# partes_proyecto.net
KiCad netlist of a schematic drawn in Altium Designer
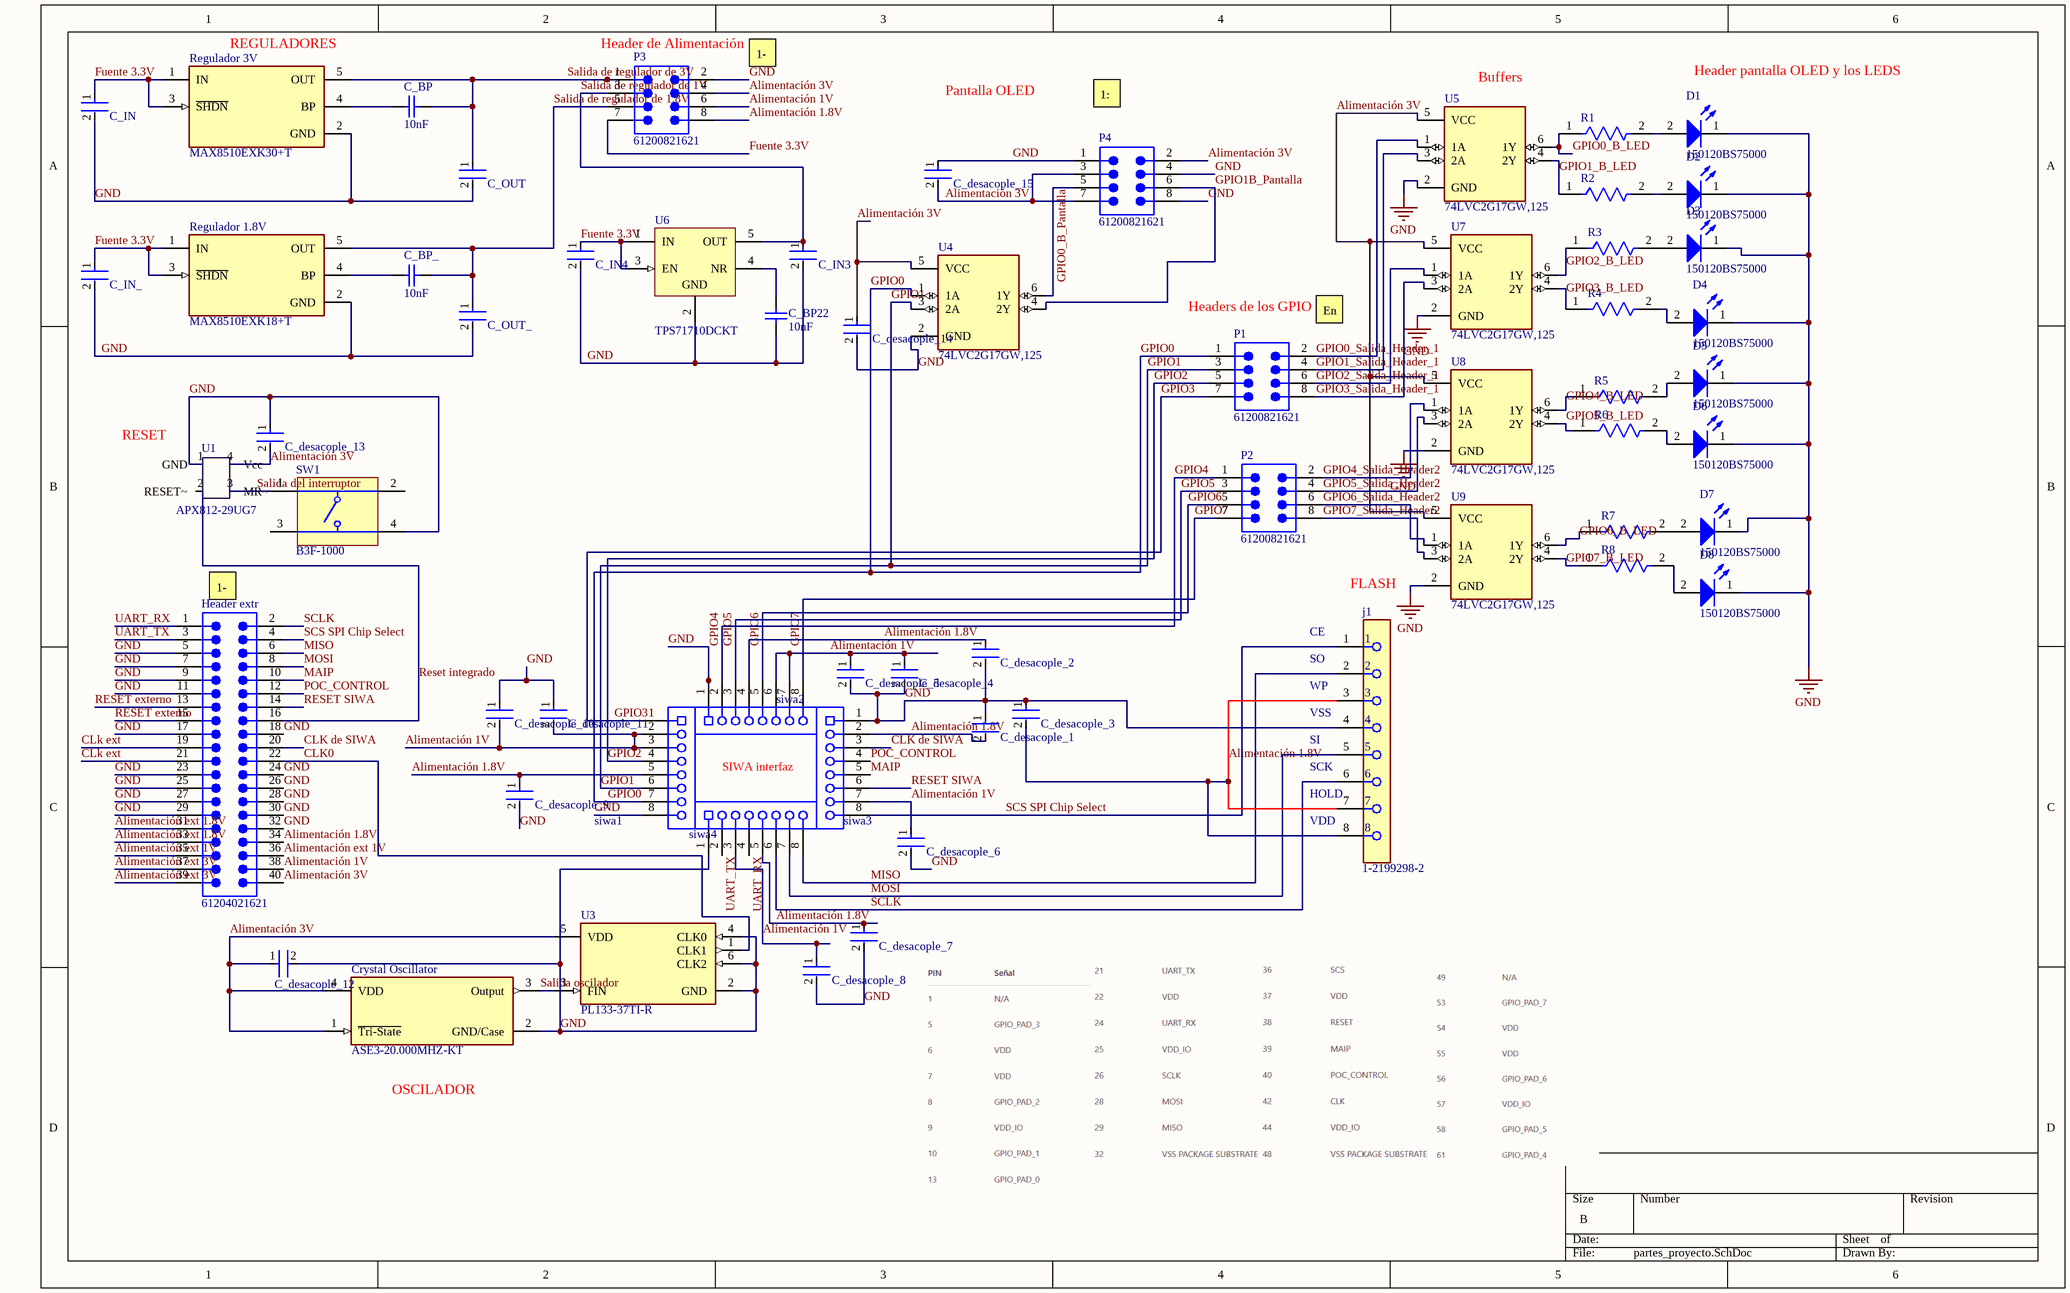
[diagram p0: partes_proyecto.SchDoc]

(export (version "E")
  (design (tool "Eeschema 10.0.6"))
  (components
    (comp (ref "Crystal Oscillator")
      (value "ASE3-20.000MHZ-KT")
      (footprint "FP-ASE3-MFG")
      (description "XTAL OSC XO 20.0000MHZ CMOS SMD")
      (libsource (lib "Altium Content Vault") (part "37c4c26fe5ae6223af2046a137c0b30"))
    )
    (comp (ref "C_BP")
      (value "10nF")
      (footprint "CAPC2013X100X50NL20T25")
      (fields (field (name "PART NUMBER") "C0805F103K5RACTU") (field (name "MANUFACTURER") "Kemet"))
      (libsource (lib "Altium Content Vault") (part "CAP"))
    )
    (comp (ref "C_BP22")
      (value "10nF")
      (footprint "CAPC2013X100X50NL20T25")
      (fields (field (name "PART NUMBER") "C0805F103K5RACTU") (field (name "MANUFACTURER") "Kemet"))
      (libsource (lib "Altium Content Vault") (part "CAP"))
    )
    (comp (ref "C_BP_")
      (value "10nF")
      (footprint "CAPC2013X100X50NL20T25")
      (fields (field (name "PART NUMBER") "C0805F103K5RACTU") (field (name "MANUFACTURER") "Kemet"))
      (libsource (lib "Altium Content Vault") (part "CAP"))
    )
    (comp (ref "C_desacople_1")
      (value "CC0603KRX7R7BB104")
      (footprint "FP-CC0603-DA-MFG")
      (description "CAP CER 0.1UF 16V X7R 0603")
      (fields
        (field (name "OCTOPART") "https://octopart.com/cc0603krx7r7bb104-yageo-192941")
        (field (name "TOLERANCE") "0.1")
      )
      (libsource (lib "Altium Content Vault") (part "11868f565c42a9108669ba33697ecf6"))
    )
    (comp (ref "C_desacople_2")
      (value "CC0603KRX7R7BB104")
      (footprint "FP-CC0603-DA-MFG")
      (description "CAP CER 0.1UF 16V X7R 0603")
      (fields
        (field (name "OCTOPART") "https://octopart.com/cc0603krx7r7bb104-yageo-192941")
        (field (name "TOLERANCE") "0.1")
      )
      (libsource (lib "Altium Content Vault") (part "11868f565c42a9108669ba33697ecf6"))
    )
    (comp (ref "C_desacople_3")
      (value "CC0603KRX7R7BB104")
      (footprint "FP-CC0603-DA-MFG")
      (description "CAP CER 0.1UF 16V X7R 0603")
      (fields
        (field (name "OCTOPART") "https://octopart.com/cc0603krx7r7bb104-yageo-192941")
        (field (name "TOLERANCE") "0.1")
      )
      (libsource (lib "Altium Content Vault") (part "11868f565c42a9108669ba33697ecf6"))
    )
    (comp (ref "C_desacople_4")
      (value "CC0603KRX7R7BB104")
      (footprint "FP-CC0603-DA-MFG")
      (description "CAP CER 0.1UF 16V X7R 0603")
      (fields
        (field (name "OCTOPART") "https://octopart.com/cc0603krx7r7bb104-yageo-192941")
        (field (name "TOLERANCE") "0.1")
      )
      (libsource (lib "Altium Content Vault") (part "11868f565c42a9108669ba33697ecf6"))
    )
    (comp (ref "C_desacople_5")
      (value "CC0603KRX7R7BB104")
      (footprint "FP-CC0603-DA-MFG")
      (description "CAP CER 0.1UF 16V X7R 0603")
      (fields
        (field (name "OCTOPART") "https://octopart.com/cc0603krx7r7bb104-yageo-192941")
        (field (name "TOLERANCE") "0.1")
      )
      (libsource (lib "Altium Content Vault") (part "11868f565c42a9108669ba33697ecf6"))
    )
    (comp (ref "C_desacople_6")
      (value "CC0603KRX7R7BB104")
      (footprint "FP-CC0603-DA-MFG")
      (description "CAP CER 0.1UF 16V X7R 0603")
      (fields
        (field (name "OCTOPART") "https://octopart.com/cc0603krx7r7bb104-yageo-192941")
        (field (name "TOLERANCE") "0.1")
      )
      (libsource (lib "Altium Content Vault") (part "11868f565c42a9108669ba33697ecf6"))
    )
    (comp (ref "C_desacople_7")
      (value "CC0603KRX7R7BB104")
      (footprint "FP-CC0603-DA-MFG")
      (description "CAP CER 0.1UF 16V X7R 0603")
      (fields
        (field (name "OCTOPART") "https://octopart.com/cc0603krx7r7bb104-yageo-192941")
        (field (name "TOLERANCE") "0.1")
      )
      (libsource (lib "Altium Content Vault") (part "11868f565c42a9108669ba33697ecf6"))
    )
    (comp (ref "C_desacople_8")
      (value "CC0603KRX7R7BB104")
      (footprint "FP-CC0603-DA-MFG")
      (description "CAP CER 0.1UF 16V X7R 0603")
      (fields
        (field (name "OCTOPART") "https://octopart.com/cc0603krx7r7bb104-yageo-192941")
        (field (name "TOLERANCE") "0.1")
      )
      (libsource (lib "Altium Content Vault") (part "11868f565c42a9108669ba33697ecf6"))
    )
    (comp (ref "C_desacople_9")
      (value "CC0603KRX7R7BB104")
      (footprint "FP-CC0603-DA-MFG")
      (description "CAP CER 0.1UF 16V X7R 0603")
      (fields
        (field (name "OCTOPART") "https://octopart.com/cc0603krx7r7bb104-yageo-192941")
        (field (name "TOLERANCE") "0.1")
      )
      (libsource (lib "Altium Content Vault") (part "11868f565c42a9108669ba33697ecf6"))
    )
    (comp (ref "C_desacople_10")
      (value "CC0603KRX7R7BB104")
      (footprint "FP-CC0603-DA-MFG")
      (description "CAP CER 0.1UF 16V X7R 0603")
      (fields
        (field (name "OCTOPART") "https://octopart.com/cc0603krx7r7bb104-yageo-192941")
        (field (name "TOLERANCE") "0.1")
      )
      (libsource (lib "Altium Content Vault") (part "11868f565c42a9108669ba33697ecf6"))
    )
    (comp (ref "C_desacople_11")
      (value "CC0603KRX7R7BB104")
      (footprint "FP-CC0603-DA-MFG")
      (description "CAP CER 0.1UF 16V X7R 0603")
      (fields
        (field (name "OCTOPART") "https://octopart.com/cc0603krx7r7bb104-yageo-192941")
        (field (name "TOLERANCE") "0.1")
      )
      (libsource (lib "Altium Content Vault") (part "11868f565c42a9108669ba33697ecf6"))
    )
    (comp (ref "C_desacople_12")
      (value "CC0603KRX7R7BB104")
      (footprint "FP-CC0603-DA-MFG")
      (description "CAP CER 0.1UF 16V X7R 0603")
      (fields
        (field (name "OCTOPART") "https://octopart.com/cc0603krx7r7bb104-yageo-192941")
        (field (name "TOLERANCE") "0.1")
      )
      (libsource (lib "Altium Content Vault") (part "11868f565c42a9108669ba33697ecf6"))
    )
    (comp (ref "C_desacople_13")
      (value "CC0603KRX7R7BB104")
      (footprint "FP-CC0603-DA-MFG")
      (description "CAP CER 0.1UF 16V X7R 0603")
      (fields
        (field (name "OCTOPART") "https://octopart.com/cc0603krx7r7bb104-yageo-192941")
        (field (name "TOLERANCE") "0.1")
      )
      (libsource (lib "Altium Content Vault") (part "11868f565c42a9108669ba33697ecf6"))
    )
    (comp (ref "C_desacople_14")
      (value "CC0603KRX7R7BB104")
      (footprint "FP-CC0603-DA-MFG")
      (description "CAP CER 0.1UF 16V X7R 0603")
      (fields
        (field (name "OCTOPART") "https://octopart.com/cc0603krx7r7bb104-yageo-192941")
        (field (name "TOLERANCE") "0.1")
      )
      (libsource (lib "Altium Content Vault") (part "11868f565c42a9108669ba33697ecf6"))
    )
    (comp (ref "C_desacople_15")
      (value "CC0603KRX7R7BB104")
      (footprint "FP-CC0603-DA-MFG")
      (description "CAP CER 0.1UF 16V X7R 0603")
      (fields
        (field (name "OCTOPART") "https://octopart.com/cc0603krx7r7bb104-yageo-192941")
        (field (name "TOLERANCE") "0.1")
      )
      (libsource (lib "Altium Content Vault") (part "11868f565c42a9108669ba33697ecf6"))
    )
    (comp (ref "C_IN")
      (value "CC0603KRX7R7BB104")
      (footprint "FP-CC0603-DA-MFG")
      (description "CAP CER 0.1UF 16V X7R 0603")
      (fields
        (field (name "OCTOPART") "https://octopart.com/cc0603krx7r7bb104-yageo-192941")
        (field (name "TOLERANCE") "0.1")
      )
      (libsource (lib "Altium Content Vault") (part "11868f565c42a9108669ba33697ecf6"))
    )
    (comp (ref "C_IN3")
      (value "CC0603KRX7R7BB104")
      (footprint "FP-CC0603-DA-MFG")
      (description "CAP CER 0.1UF 16V X7R 0603")
      (fields
        (field (name "OCTOPART") "https://octopart.com/cc0603krx7r7bb104-yageo-192941")
        (field (name "TOLERANCE") "0.1")
      )
      (libsource (lib "Altium Content Vault") (part "11868f565c42a9108669ba33697ecf6"))
    )
    (comp (ref "C_IN4")
      (value "CC0603KRX7R7BB104")
      (footprint "FP-CC0603-DA-MFG")
      (description "CAP CER 0.1UF 16V X7R 0603")
      (fields
        (field (name "OCTOPART") "https://octopart.com/cc0603krx7r7bb104-yageo-192941")
        (field (name "TOLERANCE") "0.1")
      )
      (libsource (lib "Altium Content Vault") (part "11868f565c42a9108669ba33697ecf6"))
    )
    (comp (ref "C_IN_")
      (value "CC0603KRX7R7BB104")
      (footprint "FP-CC0603-DA-MFG")
      (description "CAP CER 0.1UF 16V X7R 0603")
      (fields
        (field (name "OCTOPART") "https://octopart.com/cc0603krx7r7bb104-yageo-192941")
        (field (name "TOLERANCE") "0.1")
      )
      (libsource (lib "Altium Content Vault") (part "11868f565c42a9108669ba33697ecf6"))
    )
    (comp (ref "C_OUT")
      (value "CC0603KRX7R7BB104")
      (footprint "FP-CC0603-DA-MFG")
      (description "CAP CER 0.1UF 16V X7R 0603")
      (fields
        (field (name "OCTOPART") "https://octopart.com/cc0603krx7r7bb104-yageo-192941")
        (field (name "TOLERANCE") "0.1")
      )
      (libsource (lib "Altium Content Vault") (part "11868f565c42a9108669ba33697ecf6"))
    )
    (comp (ref "C_OUT_")
      (value "CC0603KRX7R7BB104")
      (footprint "FP-CC0603-DA-MFG")
      (description "CAP CER 0.1UF 16V X7R 0603")
      (fields
        (field (name "OCTOPART") "https://octopart.com/cc0603krx7r7bb104-yageo-192941")
        (field (name "TOLERANCE") "0.1")
      )
      (libsource (lib "Altium Content Vault") (part "11868f565c42a9108669ba33697ecf6"))
    )
    (comp (ref "D1")
      (value "150120BS75000")
      (footprint "WL-SMCW_1206_150120xx75000")
      (description "WL-SMCW SMT Mono-Color Chip LED Waterclear")
      (libsource (lib "Altium Content Vault") (part "LED_Blue_2A-1K"))
    )
    (comp (ref "D2")
      (value "150120BS75000")
      (footprint "WL-SMCW_1206_150120xx75000")
      (description "WL-SMCW SMT Mono-Color Chip LED Waterclear")
      (libsource (lib "Altium Content Vault") (part "LED_Blue_2A-1K"))
    )
    (comp (ref "D3")
      (value "150120BS75000")
      (footprint "WL-SMCW_1206_150120xx75000")
      (description "WL-SMCW SMT Mono-Color Chip LED Waterclear")
      (libsource (lib "Altium Content Vault") (part "LED_Blue_2A-1K"))
    )
    (comp (ref "D4")
      (value "150120BS75000")
      (footprint "WL-SMCW_1206_150120xx75000")
      (description "WL-SMCW SMT Mono-Color Chip LED Waterclear")
      (libsource (lib "Altium Content Vault") (part "LED_Blue_2A-1K"))
    )
    (comp (ref "D5")
      (value "150120BS75000")
      (footprint "WL-SMCW_1206_150120xx75000")
      (description "WL-SMCW SMT Mono-Color Chip LED Waterclear")
      (libsource (lib "Altium Content Vault") (part "LED_Blue_2A-1K"))
    )
    (comp (ref "D6")
      (value "150120BS75000")
      (footprint "WL-SMCW_1206_150120xx75000")
      (description "WL-SMCW SMT Mono-Color Chip LED Waterclear")
      (libsource (lib "Altium Content Vault") (part "LED_Blue_2A-1K"))
    )
    (comp (ref "D7")
      (value "150120BS75000")
      (footprint "WL-SMCW_1206_150120xx75000")
      (description "WL-SMCW SMT Mono-Color Chip LED Waterclear")
      (libsource (lib "Altium Content Vault") (part "LED_Blue_2A-1K"))
    )
    (comp (ref "D8")
      (value "150120BS75000")
      (footprint "WL-SMCW_1206_150120xx75000")
      (description "WL-SMCW SMT Mono-Color Chip LED Waterclear")
      (libsource (lib "Altium Content Vault") (part "LED_Blue_2A-1K"))
    )
    (comp (ref "Header extr")
      (value "61204021621")
      (footprint "61204021621")
      (libsource (lib "Altium Content Vault") (part "Header_Male_2R_40P"))
    )
    (comp (ref "j1")
      (value "1-2199298-2")
      (footprint "FP-1-2199298-2-MFG")
      (description "CONN IC DIP SOCKET 8POS TIN")
      (libsource (lib "Altium Content Vault") (part "b0a0b555dd3abf3683e7c330df25cc4"))
    )
    (comp (ref "P1")
      (value "61200821621")
      (footprint "61200821621")
      (libsource (lib "Altium Content Vault") (part "Header_Male_2R_08P"))
    )
    (comp (ref "P2")
      (value "61200821621")
      (footprint "61200821621")
      (libsource (lib "Altium Content Vault") (part "Header_Male_2R_08P"))
    )
    (comp (ref "P3")
      (value "61200821621")
      (footprint "61200821621")
      (libsource (lib "Altium Content Vault") (part "Header_Male_2R_08P"))
    )
    (comp (ref "P4")
      (value "61200821621")
      (footprint "61200821621")
      (libsource (lib "Altium Content Vault") (part "Header_Male_2R_08P"))
    )
    (comp (ref "R1")
      (value "10")
      (footprint "FP-MCT0603-IPC_A")
      (description "RES SMD 100 OHM 1% 1/8W 0603")
      (fields (field (name "TOLERANCE") "0.1%"))
      (libsource (lib "Altium Content Vault") (part "1029c3af85768c4190bb7ad29bc67b5"))
    )
    (comp (ref "R2")
      (value "10")
      (footprint "FP-MCT0603-IPC_A")
      (description "RES SMD 100 OHM 1% 1/8W 0603")
      (fields (field (name "TOLERANCE") "0.1%"))
      (libsource (lib "Altium Content Vault") (part "1029c3af85768c4190bb7ad29bc67b5"))
    )
    (comp (ref "R3")
      (value "10")
      (footprint "FP-MCT0603-IPC_A")
      (description "RES SMD 100 OHM 1% 1/8W 0603")
      (fields (field (name "TOLERANCE") "0.1%"))
      (libsource (lib "Altium Content Vault") (part "1029c3af85768c4190bb7ad29bc67b5"))
    )
    (comp (ref "R4")
      (value "10")
      (footprint "FP-MCT0603-IPC_A")
      (description "RES SMD 100 OHM 1% 1/8W 0603")
      (fields (field (name "TOLERANCE") "0.1%"))
      (libsource (lib "Altium Content Vault") (part "1029c3af85768c4190bb7ad29bc67b5"))
    )
    (comp (ref "R5")
      (value "10")
      (footprint "FP-MCT0603-IPC_A")
      (description "RES SMD 100 OHM 1% 1/8W 0603")
      (fields (field (name "TOLERANCE") "0.1%"))
      (libsource (lib "Altium Content Vault") (part "1029c3af85768c4190bb7ad29bc67b5"))
    )
    (comp (ref "R6")
      (value "10")
      (footprint "FP-MCT0603-IPC_A")
      (description "RES SMD 100 OHM 1% 1/8W 0603")
      (fields (field (name "TOLERANCE") "0.1%"))
      (libsource (lib "Altium Content Vault") (part "1029c3af85768c4190bb7ad29bc67b5"))
    )
    (comp (ref "R7")
      (value "10")
      (footprint "FP-MCT0603-IPC_A")
      (description "RES SMD 100 OHM 1% 1/8W 0603")
      (fields (field (name "TOLERANCE") "0.1%"))
      (libsource (lib "Altium Content Vault") (part "1029c3af85768c4190bb7ad29bc67b5"))
    )
    (comp (ref "R8")
      (value "10")
      (footprint "FP-MCT0603-IPC_A")
      (description "RES SMD 100 OHM 1% 1/8W 0603")
      (fields (field (name "TOLERANCE") "0.1%"))
      (libsource (lib "Altium Content Vault") (part "1029c3af85768c4190bb7ad29bc67b5"))
    )
    (comp (ref "Regulador 1.8V")
      (value "MAX8510EXK18+T")
      (footprint "FP-X5-1-MFG")
      (description "IC REG LINEAR 1.8V 120MA SC70-5")
      (libsource (lib "Altium Content Vault") (part "355d6218c957986cfc1b3588039a240"))
    )
    (comp (ref "Regulador 3V")
      (value "MAX8510EXK30+T")
      (footprint "FP-X5-1-MFG")
      (description "IC REG LINEAR 3V 120MA SC70-5")
      (libsource (lib "Altium Content Vault") (part "355d6218c957986cfc1b3588039a240"))
    )
    (comp (ref "siwa1")
      (value "PPPC081LFBN-RC")
      (footprint "SLIN-PPPC081LFBN-RC_V")
      (libsource (lib "") (part "CN-1P-F-R8_2"))
    )
    (comp (ref "siwa2")
      (value "PPPC081LFBN-RC")
      (footprint "SLIN-PPPC081LFBN-RC_V")
      (libsource (lib "") (part "CN-1P-F-R8_1"))
    )
    (comp (ref "siwa3")
      (value "PPPC081LFBN-RC")
      (footprint "SLIN-PPPC081LFBN-RC_V")
      (libsource (lib "") (part "CN-1P-F-R8_3"))
    )
    (comp (ref "siwa4")
      (value "PPPC081LFBN-RC")
      (footprint "SLIN-PPPC081LFBN-RC_V")
      (libsource (lib "Altium Content Vault") (part "CN-1P-F-R8"))
    )
    (comp (ref "SW1")
      (value "B3F-1000")
      (footprint "OMRON-B3F-1000-4_V")
      (description "Tactile Switch, SPST-NO, 0.05 A, 5 to 24 V, -25 to 70 degC, 4-Pin THD, RoHS, Bulk")
      (libsource (lib "Altium Content Vault") (part "SW-SPST-4_A"))
    )
    (comp (ref "U1")
      (value "APX812-29UG7")
      (footprint "APX812-29UG7")
      (description "4-Pin Microprocessor Supervisor With Manual Reset. SOT143.")
      (libsource (lib "Schlib1") (part "APX812-29UG7"))
    )
    (comp (ref "U3")
      (value "PL133-37TI-R")
      (footprint "FP-SOT23-6LD-PL-1-IPC_A")
      (description "IC CLK BUFFER 1:3 150MHZ 6SOT23")
      (libsource (lib "Altium Content Vault") (part "fd8087dcb4da491d5d9bef7da23e705"))
    )
    (comp (ref "U4")
      (value "74LVC2G17GW,125")
      (footprint "SOT363_INFINEON")
      (libsource (lib "Schlib1") (part "74LVC2G17GW,125"))
    )
    (comp (ref "U5")
      (value "74LVC2G17GW,125")
      (footprint "SOT363_INFINEON")
      (libsource (lib "Schlib1") (part "74LVC2G17GW,125"))
    )
    (comp (ref "U6")
      (value "TPS71710DCKT")
      (footprint "DCK0005A_M")
      (fields (field (name "MANUFACTURER") "Texas Instruments"))
      (libsource (lib "Altium Content Vault") (part "TI-TPS79NXX-YYSOT5"))
    )
    (comp (ref "U7")
      (value "74LVC2G17GW,125")
      (footprint "SOT363_INFINEON")
      (libsource (lib "Schlib1") (part "74LVC2G17GW,125"))
    )
    (comp (ref "U8")
      (value "74LVC2G17GW,125")
      (footprint "SOT363_INFINEON")
      (libsource (lib "Schlib1") (part "74LVC2G17GW,125"))
    )
    (comp (ref "U9")
      (value "74LVC2G17GW,125")
      (footprint "SOT363_INFINEON")
      (libsource (lib "Schlib1") (part "74LVC2G17GW,125"))
    )
  )
  (nets
    (net (code "2") (name "/Alimentación 1.8V") (class "Default")
      (node (ref "C_desacople_1") (pin "2") (pinfunction "2_2") (pintype "passive"))
      (node (ref "C_desacople_2") (pin "1") (pinfunction "1_1") (pintype "passive"))
      (node (ref "C_desacople_3") (pin "2") (pinfunction "2_2") (pintype "passive"))
      (node (ref "C_desacople_7") (pin "1") (pinfunction "1_1") (pintype "passive"))
      (node (ref "C_desacople_9") (pin "1") (pinfunction "1_1") (pintype "passive"))
      (node (ref "Header extr") (pin "34") (pinfunction "34_34") (pintype "passive"))
      (node (ref "P3") (pin "8") (pinfunction "8_8") (pintype "passive"))
      (node (ref "j1") (pin "3") (pinfunction "3_3") (pintype "passive"))
      (node (ref "j1") (pin "7") (pinfunction "7_7") (pintype "passive"))
      (node (ref "j1") (pin "8") (pinfunction "8_8") (pintype "passive"))
      (node (ref "siwa1") (pin "5") (pinfunction "5_5") (pintype "passive"))
      (node (ref "siwa2") (pin "4") (pinfunction "4_4") (pintype "passive"))
      (node (ref "siwa3") (pin "2") (pinfunction "2_2") (pintype "passive"))
      (node (ref "siwa4") (pin "5") (pinfunction "5_5") (pintype "passive"))
    )
    (net (code "3") (name "/Alimentación 1V") (class "Default")
      (node (ref "C_desacople_10") (pin "2") (pinfunction "2_2") (pintype "passive"))
      (node (ref "C_desacople_11") (pin "2") (pinfunction "2_2") (pintype "passive"))
      (node (ref "C_desacople_4") (pin "1") (pinfunction "1_1") (pintype "passive"))
      (node (ref "C_desacople_5") (pin "1") (pinfunction "1_1") (pintype "passive"))
      (node (ref "C_desacople_6") (pin "1") (pinfunction "1_1") (pintype "passive"))
      (node (ref "C_desacople_8") (pin "1") (pinfunction "1_1") (pintype "passive"))
      (node (ref "Header extr") (pin "38") (pinfunction "38_38") (pintype "passive"))
      (node (ref "P3") (pin "6") (pinfunction "6_6") (pintype "passive"))
      (node (ref "siwa1") (pin "2") (pinfunction "2_2") (pintype "passive"))
      (node (ref "siwa1") (pin "3") (pinfunction "3_3") (pintype "passive"))
      (node (ref "siwa2") (pin "6") (pinfunction "6_6") (pintype "passive"))
      (node (ref "siwa2") (pin "7") (pinfunction "7_7") (pintype "passive"))
      (node (ref "siwa3") (pin "7") (pinfunction "7_7") (pintype "passive"))
      (node (ref "siwa4") (pin "3") (pinfunction "3_3") (pintype "passive"))
    )
    (net (code "4") (name "/Alimentación 3V") (class "Default")
      (node (ref "C_desacople_12") (pin "1") (pinfunction "1_1") (pintype "passive"))
      (node (ref "C_desacople_13") (pin "2") (pinfunction "2_2") (pintype "passive"))
      (node (ref "C_desacople_14") (pin "1") (pinfunction "1_1") (pintype "passive"))
      (node (ref "C_desacople_15") (pin "2") (pinfunction "2_2") (pintype "passive"))
      (node (ref "Crystal Oscillator") (pin "1") (pinfunction "~{Tri-State}_1") (pintype "input"))
      (node (ref "Crystal Oscillator") (pin "4") (pinfunction "VDD_4") (pintype "power_in"))
      (node (ref "Header extr") (pin "40") (pinfunction "40_40") (pintype "passive"))
      (node (ref "P3") (pin "4") (pinfunction "4_4") (pintype "passive"))
      (node (ref "P4") (pin "2") (pinfunction "2_2") (pintype "passive"))
      (node (ref "P4") (pin "3") (pinfunction "3_3") (pintype "passive"))
      (node (ref "P4") (pin "7") (pinfunction "7_7") (pintype "passive"))
      (node (ref "U1") (pin "4") (pinfunction "Vcc_4") (pintype "passive"))
      (node (ref "U3") (pin "5") (pinfunction "VDD_5") (pintype "power_in"))
      (node (ref "U4") (pin "5") (pinfunction "VCC_5") (pintype "power_in"))
      (node (ref "U5") (pin "5") (pinfunction "VCC_5") (pintype "power_in"))
      (node (ref "U7") (pin "5") (pinfunction "VCC_5") (pintype "power_in"))
      (node (ref "U8") (pin "5") (pinfunction "VCC_5") (pintype "power_in"))
      (node (ref "U9") (pin "5") (pinfunction "VCC_5") (pintype "power_in"))
    )
    (net (code "5") (name "/Alimentación ext 1.8V") (class "Default")
      (node (ref "Header extr") (pin "31") (pinfunction "31_31") (pintype "passive"))
      (node (ref "Header extr") (pin "33") (pinfunction "33_33") (pintype "passive"))
    )
    (net (code "6") (name "/Alimentación ext 1V") (class "Default")
      (node (ref "Header extr") (pin "35") (pinfunction "35_35") (pintype "passive"))
      (node (ref "Header extr") (pin "36") (pinfunction "36_36") (pintype "passive"))
    )
    (net (code "7") (name "/Alimentación ext 3V") (class "Default")
      (node (ref "Header extr") (pin "37") (pinfunction "37_37") (pintype "passive"))
      (node (ref "Header extr") (pin "39") (pinfunction "39_39") (pintype "passive"))
    )
    (net (code "8") (name "/CLK de SIWA") (class "Default")
      (node (ref "Header extr") (pin "20") (pinfunction "20_20") (pintype "passive"))
      (node (ref "siwa3") (pin "3") (pinfunction "3_3") (pintype "passive"))
    )
    (net (code "9") (name "/CLK0") (class "Default")
      (node (ref "Header extr") (pin "22") (pinfunction "22_22") (pintype "passive"))
      (node (ref "U3") (pin "1") (pinfunction "CLK1_1") (pintype "output"))
    )
    (net (code "10") (name "/CLk ext") (class "Default")
      (node (ref "Header extr") (pin "19") (pinfunction "19_19") (pintype "passive"))
      (node (ref "Header extr") (pin "21") (pinfunction "21_21") (pintype "passive"))
    )
    (net (code "11") (name "/Fuente 3.3V") (class "Default")
      (node (ref "C_IN") (pin "1") (pinfunction "1_1") (pintype "passive"))
      (node (ref "C_IN4") (pin "1") (pinfunction "1_1") (pintype "passive"))
      (node (ref "C_IN_") (pin "1") (pinfunction "1_1") (pintype "passive"))
      (node (ref "P3") (pin "7") (pinfunction "7_7") (pintype "passive"))
      (node (ref "Regulador 1.8V") (pin "1") (pinfunction "IN_1") (pintype "power_in"))
      (node (ref "Regulador 1.8V") (pin "3") (pinfunction "~{SHDN}_3") (pintype "input"))
      (node (ref "Regulador 3V") (pin "1") (pinfunction "IN_1") (pintype "power_in"))
      (node (ref "Regulador 3V") (pin "3") (pinfunction "~{SHDN}_3") (pintype "input"))
      (node (ref "U6") (pin "1") (pinfunction "IN_1") (pintype "power_in"))
      (node (ref "U6") (pin "3") (pinfunction "EN_3") (pintype "input"))
    )
    (net (code "12") (name "/GPIO0") (class "Default")
      (node (ref "P1") (pin "1") (pinfunction "1_1") (pintype "passive"))
      (node (ref "U4") (pin "1") (pinfunction "1A_1") (pintype "bidirectional"))
      (node (ref "siwa1") (pin "7") (pinfunction "7_7") (pintype "passive"))
    )
    (net (code "13") (name "/GPIO0_B_LED") (class "Default")
      (node (ref "R1") (pin "1") (pinfunction "1_1") (pintype "passive"))
      (node (ref "U5") (pin "6") (pinfunction "1Y_6") (pintype "bidirectional"))
    )
    (net (code "14") (name "/GPIO0_B_Pantalla") (class "Default")
      (node (ref "P4") (pin "5") (pinfunction "5_5") (pintype "passive"))
      (node (ref "U4") (pin "6") (pinfunction "1Y_6") (pintype "bidirectional"))
    )
    (net (code "15") (name "/GPIO0_Salida_Header_1") (class "Default")
      (node (ref "P1") (pin "2") (pinfunction "2_2") (pintype "passive"))
      (node (ref "U5") (pin "1") (pinfunction "1A_1") (pintype "bidirectional"))
    )
    (net (code "16") (name "/GPIO1") (class "Default")
      (node (ref "P1") (pin "3") (pinfunction "3_3") (pintype "passive"))
      (node (ref "U4") (pin "3") (pinfunction "2A_3") (pintype "bidirectional"))
      (node (ref "siwa1") (pin "6") (pinfunction "6_6") (pintype "passive"))
    )
    (net (code "17") (name "/GPIO1B_Pantalla") (class "Default")
      (node (ref "P4") (pin "6") (pinfunction "6_6") (pintype "passive"))
      (node (ref "U4") (pin "4") (pinfunction "2Y_4") (pintype "bidirectional"))
    )
    (net (code "18") (name "/GPIO1_B_LED") (class "Default")
      (node (ref "R2") (pin "1") (pinfunction "1_1") (pintype "passive"))
      (node (ref "U5") (pin "4") (pinfunction "2Y_4") (pintype "bidirectional"))
    )
    (net (code "19") (name "/GPIO1_Salida_Header_1") (class "Default")
      (node (ref "P1") (pin "4") (pinfunction "4_4") (pintype "passive"))
      (node (ref "U5") (pin "3") (pinfunction "2A_3") (pintype "bidirectional"))
    )
    (net (code "20") (name "/GPIO2") (class "Default")
      (node (ref "P1") (pin "5") (pinfunction "5_5") (pintype "passive"))
      (node (ref "siwa1") (pin "4") (pinfunction "4_4") (pintype "passive"))
    )
    (net (code "21") (name "/GPIO2_B_LED") (class "Default")
      (node (ref "R3") (pin "1") (pinfunction "1_1") (pintype "passive"))
      (node (ref "U7") (pin "6") (pinfunction "1Y_6") (pintype "bidirectional"))
    )
    (net (code "22") (name "/GPIO2_Salida_Header_1") (class "Default")
      (node (ref "P1") (pin "6") (pinfunction "6_6") (pintype "passive"))
      (node (ref "U7") (pin "1") (pinfunction "1A_1") (pintype "bidirectional"))
    )
    (net (code "23") (name "/GPIO3") (class "Default")
      (node (ref "P1") (pin "7") (pinfunction "7_7") (pintype "passive"))
      (node (ref "siwa1") (pin "1") (pinfunction "1_1") (pintype "passive"))
    )
    (net (code "24") (name "/GPIO3_B_LED") (class "Default")
      (node (ref "R4") (pin "1") (pinfunction "1_1") (pintype "passive"))
      (node (ref "U7") (pin "4") (pinfunction "2Y_4") (pintype "bidirectional"))
    )
    (net (code "25") (name "/GPIO3_Salida_Header_1") (class "Default")
      (node (ref "P1") (pin "8") (pinfunction "8_8") (pintype "passive"))
      (node (ref "U7") (pin "3") (pinfunction "2A_3") (pintype "bidirectional"))
    )
    (net (code "26") (name "/GPIO4") (class "Default")
      (node (ref "P2") (pin "1") (pinfunction "1_1") (pintype "passive"))
      (node (ref "siwa2") (pin "2") (pinfunction "2_2") (pintype "passive"))
    )
    (net (code "27") (name "/GPIO4_B_LED") (class "Default")
      (node (ref "R5") (pin "1") (pinfunction "1_1") (pintype "passive"))
      (node (ref "U8") (pin "6") (pinfunction "1Y_6") (pintype "bidirectional"))
    )
    (net (code "28") (name "/GPIO4_Salida_Header2") (class "Default")
      (node (ref "P2") (pin "2") (pinfunction "2_2") (pintype "passive"))
      (node (ref "U8") (pin "1") (pinfunction "1A_1") (pintype "bidirectional"))
    )
    (net (code "29") (name "/GPIO5") (class "Default")
      (node (ref "P2") (pin "3") (pinfunction "3_3") (pintype "passive"))
      (node (ref "siwa2") (pin "3") (pinfunction "3_3") (pintype "passive"))
    )
    (net (code "30") (name "/GPIO5_B_LED") (class "Default")
      (node (ref "R6") (pin "1") (pinfunction "1_1") (pintype "passive"))
      (node (ref "U8") (pin "4") (pinfunction "2Y_4") (pintype "bidirectional"))
    )
    (net (code "31") (name "/GPIO5_Salida_Header2") (class "Default")
      (node (ref "P2") (pin "4") (pinfunction "4_4") (pintype "passive"))
      (node (ref "U8") (pin "3") (pinfunction "2A_3") (pintype "bidirectional"))
    )
    (net (code "32") (name "/GPIO6") (class "Default")
      (node (ref "P2") (pin "5") (pinfunction "5_5") (pintype "passive"))
      (node (ref "siwa2") (pin "5") (pinfunction "5_5") (pintype "passive"))
    )
    (net (code "33") (name "/GPIO6_B_LED") (class "Default")
      (node (ref "R7") (pin "1") (pinfunction "1_1") (pintype "passive"))
      (node (ref "U9") (pin "6") (pinfunction "1Y_6") (pintype "bidirectional"))
    )
    (net (code "34") (name "/GPIO6_Salida_Header2") (class "Default")
      (node (ref "P2") (pin "6") (pinfunction "6_6") (pintype "passive"))
      (node (ref "U9") (pin "1") (pinfunction "1A_1") (pintype "bidirectional"))
    )
    (net (code "35") (name "/GPIO7") (class "Default")
      (node (ref "P2") (pin "7") (pinfunction "7_7") (pintype "passive"))
      (node (ref "siwa2") (pin "8") (pinfunction "8_8") (pintype "passive"))
    )
    (net (code "36") (name "/GPIO7_B_LED") (class "Default")
      (node (ref "R8") (pin "1") (pinfunction "1_1") (pintype "passive"))
      (node (ref "U9") (pin "4") (pinfunction "2Y_4") (pintype "bidirectional"))
    )
    (net (code "37") (name "/GPIO7_Salida_Header2") (class "Default")
      (node (ref "P2") (pin "8") (pinfunction "8_8") (pintype "passive"))
      (node (ref "U9") (pin "3") (pinfunction "2A_3") (pintype "bidirectional"))
    )
    (net (code "38") (name "/MAIP") (class "Default")
      (node (ref "Header extr") (pin "10") (pinfunction "10_10") (pintype "passive"))
      (node (ref "siwa3") (pin "5") (pinfunction "5_5") (pintype "passive"))
    )
    (net (code "39") (name "/MISO") (class "Default")
      (node (ref "Header extr") (pin "6") (pinfunction "6_6") (pintype "passive"))
      (node (ref "j1") (pin "2") (pinfunction "2_2") (pintype "passive"))
      (node (ref "siwa4") (pin "8") (pinfunction "8_8") (pintype "passive"))
    )
    (net (code "40") (name "/MOSI") (class "Default")
      (node (ref "Header extr") (pin "8") (pinfunction "8_8") (pintype "passive"))
      (node (ref "j1") (pin "5") (pinfunction "5_5") (pintype "passive"))
      (node (ref "siwa4") (pin "7") (pinfunction "7_7") (pintype "passive"))
    )
    (net (code "41") (name "/POC_CONTROL") (class "Default")
      (node (ref "Header extr") (pin "12") (pinfunction "12_12") (pintype "passive"))
      (node (ref "siwa3") (pin "4") (pinfunction "4_4") (pintype "passive"))
    )
    (net (code "42") (name "/RESET SIWA") (class "Default")
      (node (ref "Header extr") (pin "14") (pinfunction "14_14") (pintype "passive"))
      (node (ref "siwa3") (pin "6") (pinfunction "6_6") (pintype "passive"))
    )
    (net (code "43") (name "/RESET externo") (class "Default")
      (node (ref "Header extr") (pin "13") (pinfunction "13_13") (pintype "passive"))
      (node (ref "Header extr") (pin "15") (pinfunction "15_15") (pintype "passive"))
    )
    (net (code "44") (name "/Reset integrado") (class "Default")
      (node (ref "Header extr") (pin "16") (pinfunction "16_16") (pintype "passive"))
      (node (ref "U1") (pin "2") (pinfunction "RESET~_2") (pintype "passive"))
    )
    (net (code "45") (name "/SCLK") (class "Default")
      (node (ref "Header extr") (pin "2") (pinfunction "2_2") (pintype "passive"))
      (node (ref "j1") (pin "6") (pinfunction "6_6") (pintype "passive"))
      (node (ref "siwa4") (pin "6") (pinfunction "6_6") (pintype "passive"))
    )
    (net (code "46") (name "/SCS SPI Chip Select") (class "Default")
      (node (ref "Header extr") (pin "4") (pinfunction "4_4") (pintype "passive"))
      (node (ref "j1") (pin "1") (pinfunction "1_1") (pintype "passive"))
      (node (ref "siwa3") (pin "8") (pinfunction "8_8") (pintype "passive"))
    )
    (net (code "47") (name "/Salida de regulador de 1.8V") (class "Default")
      (node (ref "C_BP_") (pin "2") (pinfunction "2_2") (pintype "passive"))
      (node (ref "C_OUT_") (pin "1") (pinfunction "1_1") (pintype "passive"))
      (node (ref "P3") (pin "5") (pinfunction "5_5") (pintype "passive"))
      (node (ref "Regulador 1.8V") (pin "5") (pinfunction "OUT_5") (pintype "power_in"))
    )
    (net (code "48") (name "/Salida de regulador de 1V") (class "Default")
      (node (ref "C_IN3") (pin "1") (pinfunction "1_1") (pintype "passive"))
      (node (ref "P3") (pin "3") (pinfunction "3_3") (pintype "passive"))
      (node (ref "U6") (pin "5") (pinfunction "OUT_5") (pintype "power_in"))
    )
    (net (code "49") (name "/Salida de regulador de 3V") (class "Default")
      (node (ref "C_BP") (pin "2") (pinfunction "2_2") (pintype "passive"))
      (node (ref "C_OUT") (pin "1") (pinfunction "1_1") (pintype "passive"))
      (node (ref "P3") (pin "1") (pinfunction "1_1") (pintype "passive"))
      (node (ref "Regulador 3V") (pin "5") (pinfunction "OUT_5") (pintype "power_in"))
    )
    (net (code "50") (name "/Salida del interruptor") (class "Default")
      (node (ref "SW1") (pin "1") (pinfunction "1_1") (pintype "passive"))
      (node (ref "U1") (pin "3") (pinfunction "MR~_3") (pintype "passive"))
    )
    (net (code "51") (name "/Salida oscilador") (class "Default")
      (node (ref "Crystal Oscillator") (pin "3") (pinfunction "Output_3") (pintype "output"))
      (node (ref "U3") (pin "3") (pinfunction "FIN_3") (pintype "input"))
    )
    (net (code "52") (name "/UART_RX") (class "Default")
      (node (ref "Header extr") (pin "1") (pinfunction "1_1") (pintype "passive"))
      (node (ref "siwa4") (pin "4") (pinfunction "4_4") (pintype "passive"))
    )
    (net (code "53") (name "/UART_TX") (class "Default")
      (node (ref "Header extr") (pin "3") (pinfunction "3_3") (pintype "passive"))
      (node (ref "siwa4") (pin "2") (pinfunction "2_2") (pintype "passive"))
    )
    (net (code "54") (name "GND") (class "Default")
      (node (ref "C_BP22") (pin "1") (pinfunction "1_1") (pintype "passive"))
      (node (ref "C_IN") (pin "2") (pinfunction "2_2") (pintype "passive"))
      (node (ref "C_IN3") (pin "2") (pinfunction "2_2") (pintype "passive"))
      (node (ref "C_IN4") (pin "2") (pinfunction "2_2") (pintype "passive"))
      (node (ref "C_IN_") (pin "2") (pinfunction "2_2") (pintype "passive"))
      (node (ref "C_OUT") (pin "2") (pinfunction "2_2") (pintype "passive"))
      (node (ref "C_OUT_") (pin "2") (pinfunction "2_2") (pintype "passive"))
      (node (ref "C_desacople_1") (pin "1") (pinfunction "1_1") (pintype "passive"))
      (node (ref "C_desacople_10") (pin "1") (pinfunction "1_1") (pintype "passive"))
      (node (ref "C_desacople_11") (pin "1") (pinfunction "1_1") (pintype "passive"))
      (node (ref "C_desacople_12") (pin "2") (pinfunction "2_2") (pintype "passive"))
      (node (ref "C_desacople_13") (pin "1") (pinfunction "1_1") (pintype "passive"))
      (node (ref "C_desacople_14") (pin "2") (pinfunction "2_2") (pintype "passive"))
      (node (ref "C_desacople_15") (pin "1") (pinfunction "1_1") (pintype "passive"))
      (node (ref "C_desacople_2") (pin "2") (pinfunction "2_2") (pintype "passive"))
      (node (ref "C_desacople_3") (pin "1") (pinfunction "1_1") (pintype "passive"))
      (node (ref "C_desacople_4") (pin "2") (pinfunction "2_2") (pintype "passive"))
      (node (ref "C_desacople_5") (pin "2") (pinfunction "2_2") (pintype "passive"))
      (node (ref "C_desacople_6") (pin "2") (pinfunction "2_2") (pintype "passive"))
      (node (ref "C_desacople_7") (pin "2") (pinfunction "2_2") (pintype "passive"))
      (node (ref "C_desacople_8") (pin "2") (pinfunction "2_2") (pintype "passive"))
      (node (ref "C_desacople_9") (pin "2") (pinfunction "2_2") (pintype "passive"))
      (node (ref "Crystal Oscillator") (pin "2") (pinfunction "GND/Case_2") (pintype "power_in"))
      (node (ref "D1") (pin "1") (pinfunction "K_1") (pintype "passive"))
      (node (ref "D2") (pin "1") (pinfunction "K_1") (pintype "passive"))
      (node (ref "D3") (pin "1") (pinfunction "K_1") (pintype "passive"))
      (node (ref "D4") (pin "1") (pinfunction "K_1") (pintype "passive"))
      (node (ref "D5") (pin "1") (pinfunction "K_1") (pintype "passive"))
      (node (ref "D6") (pin "1") (pinfunction "K_1") (pintype "passive"))
      (node (ref "D7") (pin "1") (pinfunction "K_1") (pintype "passive"))
      (node (ref "D8") (pin "1") (pinfunction "K_1") (pintype "passive"))
      (node (ref "Header extr") (pin "11") (pinfunction "11_11") (pintype "passive"))
      (node (ref "Header extr") (pin "17") (pinfunction "17_17") (pintype "passive"))
      (node (ref "Header extr") (pin "18") (pinfunction "18_18") (pintype "passive"))
      (node (ref "Header extr") (pin "23") (pinfunction "23_23") (pintype "passive"))
      (node (ref "Header extr") (pin "24") (pinfunction "24_24") (pintype "passive"))
      (node (ref "Header extr") (pin "25") (pinfunction "25_25") (pintype "passive"))
      (node (ref "Header extr") (pin "26") (pinfunction "26_26") (pintype "passive"))
      (node (ref "Header extr") (pin "27") (pinfunction "27_27") (pintype "passive"))
      (node (ref "Header extr") (pin "28") (pinfunction "28_28") (pintype "passive"))
      (node (ref "Header extr") (pin "29") (pinfunction "29_29") (pintype "passive"))
      (node (ref "Header extr") (pin "30") (pinfunction "30_30") (pintype "passive"))
      (node (ref "Header extr") (pin "32") (pinfunction "32_32") (pintype "passive"))
      (node (ref "Header extr") (pin "5") (pinfunction "5_5") (pintype "passive"))
      (node (ref "Header extr") (pin "7") (pinfunction "7_7") (pintype "passive"))
      (node (ref "Header extr") (pin "9") (pinfunction "9_9") (pintype "passive"))
      (node (ref "P3") (pin "2") (pinfunction "2_2") (pintype "passive"))
      (node (ref "P4") (pin "1") (pinfunction "1_1") (pintype "passive"))
      (node (ref "P4") (pin "4") (pinfunction "4_4") (pintype "passive"))
      (node (ref "P4") (pin "8") (pinfunction "8_8") (pintype "passive"))
      (node (ref "Regulador 1.8V") (pin "2") (pinfunction "GND_2") (pintype "power_in"))
      (node (ref "Regulador 3V") (pin "2") (pinfunction "GND_2") (pintype "power_in"))
      (node (ref "SW1") (pin "4") (pinfunction "4_4") (pintype "passive"))
      (node (ref "U1") (pin "1") (pinfunction "GND_1") (pintype "passive"))
      (node (ref "U3") (pin "2") (pinfunction "GND_2") (pintype "power_in"))
      (node (ref "U3") (pin "4") (pinfunction "CLK0_4") (pintype "input"))
      (node (ref "U3") (pin "6") (pinfunction "CLK2_6") (pintype "input"))
      (node (ref "U4") (pin "2") (pinfunction "GND_2") (pintype "power_in"))
      (node (ref "U5") (pin "2") (pinfunction "GND_2") (pintype "power_in"))
      (node (ref "U6") (pin "2") (pinfunction "GND_2") (pintype "power_in"))
      (node (ref "U7") (pin "2") (pinfunction "GND_2") (pintype "power_in"))
      (node (ref "U8") (pin "2") (pinfunction "GND_2") (pintype "power_in"))
      (node (ref "U9") (pin "2") (pinfunction "GND_2") (pintype "power_in"))
      (node (ref "j1") (pin "4") (pinfunction "4_4") (pintype "passive"))
      (node (ref "siwa1") (pin "8") (pinfunction "8_8") (pintype "passive"))
      (node (ref "siwa2") (pin "1") (pinfunction "1_1") (pintype "passive"))
      (node (ref "siwa3") (pin "1") (pinfunction "1_1") (pintype "passive"))
      (node (ref "siwa4") (pin "1") (pinfunction "1_1") (pintype "passive"))
    )
    (net (code "55") (name "Net-(D1-A)") (class "Default")
      (node (ref "D1") (pin "2") (pinfunction "A_2") (pintype "passive"))
      (node (ref "R1") (pin "2") (pinfunction "2_2") (pintype "passive"))
    )
    (net (code "56") (name "Net-(D2-A)") (class "Default")
      (node (ref "D2") (pin "2") (pinfunction "A_2") (pintype "passive"))
      (node (ref "R2") (pin "2") (pinfunction "2_2") (pintype "passive"))
    )
    (net (code "57") (name "Net-(D3-A)") (class "Default")
      (node (ref "D3") (pin "2") (pinfunction "A_2") (pintype "passive"))
      (node (ref "R3") (pin "2") (pinfunction "2_2") (pintype "passive"))
    )
    (net (code "58") (name "Net-(D4-A)") (class "Default")
      (node (ref "D4") (pin "2") (pinfunction "A_2") (pintype "passive"))
      (node (ref "R4") (pin "2") (pinfunction "2_2") (pintype "passive"))
    )
    (net (code "59") (name "Net-(D5-A)") (class "Default")
      (node (ref "D5") (pin "2") (pinfunction "A_2") (pintype "passive"))
      (node (ref "R5") (pin "2") (pinfunction "2_2") (pintype "passive"))
    )
    (net (code "60") (name "Net-(D6-A)") (class "Default")
      (node (ref "D6") (pin "2") (pinfunction "A_2") (pintype "passive"))
      (node (ref "R6") (pin "2") (pinfunction "2_2") (pintype "passive"))
    )
    (net (code "61") (name "Net-(D7-A)") (class "Default")
      (node (ref "D7") (pin "2") (pinfunction "A_2") (pintype "passive"))
      (node (ref "R7") (pin "2") (pinfunction "2_2") (pintype "passive"))
    )
    (net (code "62") (name "Net-(D8-A)") (class "Default")
      (node (ref "D8") (pin "2") (pinfunction "A_2") (pintype "passive"))
      (node (ref "R8") (pin "2") (pinfunction "2_2") (pintype "passive"))
    )
    (net (code "63") (name "Net-(Regulador 1.8V-BP)") (class "Default")
      (node (ref "C_BP_") (pin "1") (pinfunction "1_1") (pintype "passive"))
      (node (ref "Regulador 1.8V") (pin "4") (pinfunction "BP_4") (pintype "passive"))
    )
    (net (code "64") (name "Net-(Regulador 3V-BP)") (class "Default")
      (node (ref "C_BP") (pin "1") (pinfunction "1_1") (pintype "passive"))
      (node (ref "Regulador 3V") (pin "4") (pinfunction "BP_4") (pintype "passive"))
    )
    (net (code "65") (name "Net-(U6-NR)") (class "Default")
      (node (ref "C_BP22") (pin "2") (pinfunction "2_2") (pintype "passive"))
      (node (ref "U6") (pin "4") (pinfunction "NR_4") (pintype "passive"))
    )
    (net (code "66") (name "unconnected-(SW1-Pad2)") (class "Default")
      (node (ref "SW1") (pin "2") (pinfunction "2_2") (pintype "passive"))
    )
    (net (code "67") (name "unconnected-(SW1-Pad3)") (class "Default")
      (node (ref "SW1") (pin "3") (pinfunction "3_3") (pintype "passive"))
    )
  )
)
